# Driver_1.net
KiCad netlist of a schematic drawn in EAGLE
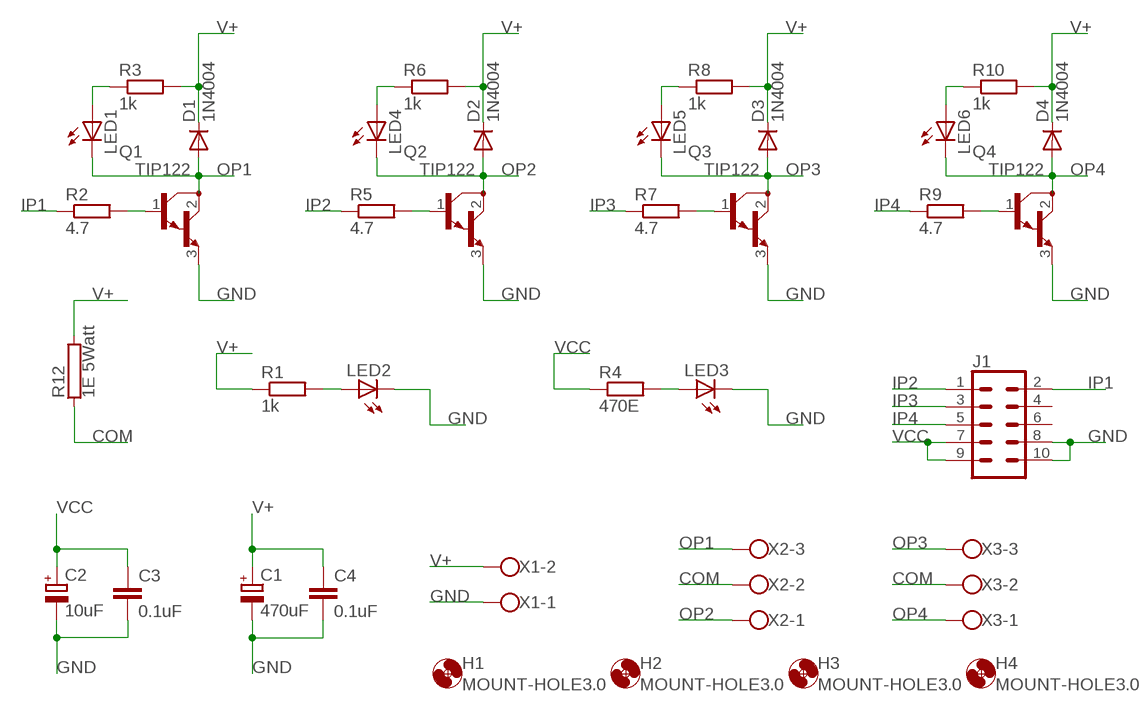
[diagram p0: schematic, sheet 1]

(export (version "E")
  (design (tool "Eeschema 10.0.6"))
  (components
    (comp (ref "C1")
      (value "470uF")
      (footprint "eagle-import:E5-8,5")
      (libsource (lib "eagle-import") (part "CPOL-EUE5-8.5"))
    )
    (comp (ref "C2")
      (value "10uF")
      (footprint "eagle-import:E2-5")
      (libsource (lib "eagle-import") (part "CPOL-EUE2-5"))
    )
    (comp (ref "C3")
      (value "0.1uF")
      (footprint "eagle-import:C025-025X050")
      (libsource (lib "eagle-import") (part "C-EU025-025X050"))
    )
    (comp (ref "C4")
      (value "0.1uF")
      (footprint "eagle-import:C025-025X050")
      (libsource (lib "eagle-import") (part "C-EU025-025X050"))
    )
    (comp (ref "D1")
      (value "1N4004")
      (footprint "eagle-import:DO41-10")
      (libsource (lib "eagle-import") (part "1N4004"))
    )
    (comp (ref "D2")
      (value "1N4004")
      (footprint "eagle-import:DO41-10")
      (libsource (lib "eagle-import") (part "1N4004"))
    )
    (comp (ref "D3")
      (value "1N4004")
      (footprint "eagle-import:DO41-10")
      (libsource (lib "eagle-import") (part "1N4004"))
    )
    (comp (ref "D4")
      (value "1N4004")
      (footprint "eagle-import:DO41-10")
      (libsource (lib "eagle-import") (part "1N4004"))
    )
    (comp (ref "H1")
      (value "MOUNT-HOLE3.0")
      (footprint "eagle-import:3,0")
      (libsource (lib "eagle-import") (part "MOUNT-HOLE3.0"))
    )
    (comp (ref "H2")
      (value "MOUNT-HOLE3.0")
      (footprint "eagle-import:3,0")
      (libsource (lib "eagle-import") (part "MOUNT-HOLE3.0"))
    )
    (comp (ref "H3")
      (value "MOUNT-HOLE3.0")
      (footprint "eagle-import:3,0")
      (libsource (lib "eagle-import") (part "MOUNT-HOLE3.0"))
    )
    (comp (ref "H4")
      (value "MOUNT-HOLE3.0")
      (footprint "eagle-import:3,0")
      (libsource (lib "eagle-import") (part "MOUNT-HOLE3.0"))
    )
    (comp (ref "J1")
      (value "CONN_05X2RAF")
      (footprint "eagle-import:2X5-RAF")
      (libsource (lib "eagle-import") (part "CONN_05X2RAF"))
    )
    (comp (ref "LED1")
      (value "LED5MM")
      (footprint "eagle-import:LED5MM")
      (libsource (lib "eagle-import") (part "LED5MM"))
    )
    (comp (ref "LED2")
      (value "LED5MM")
      (footprint "eagle-import:LED5MM")
      (libsource (lib "eagle-import") (part "LED5MM"))
    )
    (comp (ref "LED3")
      (value "LED5MM")
      (footprint "eagle-import:LED5MM")
      (libsource (lib "eagle-import") (part "LED5MM"))
    )
    (comp (ref "LED4")
      (value "LED5MM")
      (footprint "eagle-import:LED5MM")
      (libsource (lib "eagle-import") (part "LED5MM"))
    )
    (comp (ref "LED5")
      (value "LED5MM")
      (footprint "eagle-import:LED5MM")
      (libsource (lib "eagle-import") (part "LED5MM"))
    )
    (comp (ref "LED6")
      (value "LED5MM")
      (footprint "eagle-import:LED5MM")
      (libsource (lib "eagle-import") (part "LED5MM"))
    )
    (comp (ref "Q1")
      (value "TIP122")
      (footprint "eagle-import:TO220")
      (libsource (lib "eagle-import") (part "TIP122"))
    )
    (comp (ref "Q2")
      (value "TIP122")
      (footprint "eagle-import:TO220")
      (libsource (lib "eagle-import") (part "TIP122"))
    )
    (comp (ref "Q3")
      (value "TIP122")
      (footprint "eagle-import:TO220")
      (libsource (lib "eagle-import") (part "TIP122"))
    )
    (comp (ref "Q4")
      (value "TIP122")
      (footprint "eagle-import:TO220")
      (libsource (lib "eagle-import") (part "TIP122"))
    )
    (comp (ref "R1")
      (value "1k")
      (footprint "eagle-import:0207_10")
      (libsource (lib "eagle-import") (part "R-EU_0207/10"))
    )
    (comp (ref "R2")
      (value "4.7")
      (footprint "eagle-import:0207_10")
      (libsource (lib "eagle-import") (part "R-EU_0207/10"))
    )
    (comp (ref "R3")
      (value "1k")
      (footprint "eagle-import:0207_10")
      (libsource (lib "eagle-import") (part "R-EU_0207/10"))
    )
    (comp (ref "R4")
      (value "470E")
      (footprint "eagle-import:0207_10")
      (libsource (lib "eagle-import") (part "R-EU_0207/10"))
    )
    (comp (ref "R5")
      (value "4.7")
      (footprint "eagle-import:0207_10")
      (libsource (lib "eagle-import") (part "R-EU_0207/10"))
    )
    (comp (ref "R6")
      (value "1k")
      (footprint "eagle-import:0207_10")
      (libsource (lib "eagle-import") (part "R-EU_0207/10"))
    )
    (comp (ref "R7")
      (value "4.7")
      (footprint "eagle-import:0207_10")
      (libsource (lib "eagle-import") (part "R-EU_0207/10"))
    )
    (comp (ref "R8")
      (value "1k")
      (footprint "eagle-import:0207_10")
      (libsource (lib "eagle-import") (part "R-EU_0207/10"))
    )
    (comp (ref "R9")
      (value "4.7")
      (footprint "eagle-import:0207_10")
      (libsource (lib "eagle-import") (part "R-EU_0207/10"))
    )
    (comp (ref "R10")
      (value "1k")
      (footprint "eagle-import:0207_10")
      (libsource (lib "eagle-import") (part "R-EU_0207/10"))
    )
    (comp (ref "R12")
      (value "1E 5Watt")
      (footprint "eagle-import:KH208-8")
      (libsource (lib "eagle-import") (part "RKH208-8"))
    )
    (comp (ref "X1")
      (value "W237-102")
      (footprint "eagle-import:W237-102")
      (fields (field (name "MPN") "237-102"))
      (libsource (lib "eagle-import") (part "W237-102"))
    )
    (comp (ref "X2")
      (value "W237-103")
      (footprint "eagle-import:W237-103")
      (fields (field (name "MPN") "237-103"))
      (libsource (lib "eagle-import") (part "W237-103"))
    )
    (comp (ref "X3")
      (value "W237-103")
      (footprint "eagle-import:W237-103")
      (fields (field (name "MPN") "237-103"))
      (libsource (lib "eagle-import") (part "W237-103"))
    )
  )
  (nets
    (net (code "1") (name "/COM") (class "Default")
      (node (ref "R12") (pin "1") (pinfunction "1_1") (pintype "passive"))
      (node (ref "X2") (pin "2") (pinfunction "KL_2") (pintype "passive"))
      (node (ref "X3") (pin "2") (pinfunction "KL_2") (pintype "passive"))
    )
    (net (code "2") (name "/GND") (class "Default")
      (node (ref "C1") (pin "-") (pinfunction "-_-") (pintype "passive"))
      (node (ref "C2") (pin "-") (pinfunction "-_-") (pintype "passive"))
      (node (ref "C3") (pin "2") (pinfunction "2_2") (pintype "passive"))
      (node (ref "C4") (pin "2") (pinfunction "2_2") (pintype "passive"))
      (node (ref "J1") (pin "10") (pinfunction "10_10") (pintype "passive"))
      (node (ref "J1") (pin "8") (pinfunction "8_8") (pintype "passive"))
      (node (ref "LED2") (pin "K") (pinfunction "C_K") (pintype "passive"))
      (node (ref "LED3") (pin "K") (pinfunction "C_K") (pintype "passive"))
      (node (ref "Q1") (pin "3") (pinfunction "E_3") (pintype "passive"))
      (node (ref "Q2") (pin "3") (pinfunction "E_3") (pintype "passive"))
      (node (ref "Q3") (pin "3") (pinfunction "E_3") (pintype "passive"))
      (node (ref "Q4") (pin "3") (pinfunction "E_3") (pintype "passive"))
      (node (ref "X1") (pin "1") (pinfunction "KL_1") (pintype "passive"))
    )
    (net (code "3") (name "/IP1") (class "Default")
      (node (ref "J1") (pin "2") (pinfunction "2_2") (pintype "passive"))
      (node (ref "R2") (pin "1") (pinfunction "1_1") (pintype "passive"))
    )
    (net (code "4") (name "/IP2") (class "Default")
      (node (ref "J1") (pin "1") (pinfunction "1_1") (pintype "passive"))
      (node (ref "R5") (pin "1") (pinfunction "1_1") (pintype "passive"))
    )
    (net (code "5") (name "/IP3") (class "Default")
      (node (ref "J1") (pin "3") (pinfunction "3_3") (pintype "passive"))
      (node (ref "R7") (pin "1") (pinfunction "1_1") (pintype "passive"))
    )
    (net (code "6") (name "/IP4") (class "Default")
      (node (ref "J1") (pin "5") (pinfunction "5_5") (pintype "passive"))
      (node (ref "R9") (pin "1") (pinfunction "1_1") (pintype "passive"))
    )
    (net (code "7") (name "/OP1") (class "Default")
      (node (ref "D1") (pin "A") (pinfunction "A_A") (pintype "passive"))
      (node (ref "LED1") (pin "K") (pinfunction "C_K") (pintype "passive"))
      (node (ref "Q1") (pin "2") (pinfunction "C_2") (pintype "passive"))
      (node (ref "X2") (pin "3") (pinfunction "KL_3") (pintype "passive"))
    )
    (net (code "8") (name "/OP2") (class "Default")
      (node (ref "D2") (pin "A") (pinfunction "A_A") (pintype "passive"))
      (node (ref "LED4") (pin "K") (pinfunction "C_K") (pintype "passive"))
      (node (ref "Q2") (pin "2") (pinfunction "C_2") (pintype "passive"))
      (node (ref "X2") (pin "1") (pinfunction "KL_1") (pintype "passive"))
    )
    (net (code "9") (name "/OP3") (class "Default")
      (node (ref "D3") (pin "A") (pinfunction "A_A") (pintype "passive"))
      (node (ref "LED5") (pin "K") (pinfunction "C_K") (pintype "passive"))
      (node (ref "Q3") (pin "2") (pinfunction "C_2") (pintype "passive"))
      (node (ref "X3") (pin "3") (pinfunction "KL_3") (pintype "passive"))
    )
    (net (code "10") (name "/OP4") (class "Default")
      (node (ref "D4") (pin "A") (pinfunction "A_A") (pintype "passive"))
      (node (ref "LED6") (pin "K") (pinfunction "C_K") (pintype "passive"))
      (node (ref "Q4") (pin "2") (pinfunction "C_2") (pintype "passive"))
      (node (ref "X3") (pin "1") (pinfunction "KL_1") (pintype "passive"))
    )
    (net (code "11") (name "/V+") (class "Default")
      (node (ref "C1") (pin "+") (pinfunction "+_+") (pintype "passive"))
      (node (ref "C4") (pin "1") (pinfunction "1_1") (pintype "passive"))
      (node (ref "D1") (pin "C") (pinfunction "C_C") (pintype "passive"))
      (node (ref "D2") (pin "C") (pinfunction "C_C") (pintype "passive"))
      (node (ref "D3") (pin "C") (pinfunction "C_C") (pintype "passive"))
      (node (ref "D4") (pin "C") (pinfunction "C_C") (pintype "passive"))
      (node (ref "R1") (pin "1") (pinfunction "1_1") (pintype "passive"))
      (node (ref "R10") (pin "2") (pinfunction "2_2") (pintype "passive"))
      (node (ref "R12") (pin "2") (pinfunction "2_2") (pintype "passive"))
      (node (ref "R3") (pin "2") (pinfunction "2_2") (pintype "passive"))
      (node (ref "R6") (pin "2") (pinfunction "2_2") (pintype "passive"))
      (node (ref "R8") (pin "2") (pinfunction "2_2") (pintype "passive"))
      (node (ref "X1") (pin "2") (pinfunction "KL_2") (pintype "passive"))
    )
    (net (code "12") (name "/VCC") (class "Default")
      (node (ref "C2") (pin "+") (pinfunction "+_+") (pintype "passive"))
      (node (ref "C3") (pin "1") (pinfunction "1_1") (pintype "passive"))
      (node (ref "J1") (pin "7") (pinfunction "7_7") (pintype "passive"))
      (node (ref "J1") (pin "9") (pinfunction "9_9") (pintype "passive"))
      (node (ref "R4") (pin "1") (pinfunction "1_1") (pintype "passive"))
    )
    (net (code "13") (name "Net-(LED1-PadA)") (class "Default")
      (node (ref "LED1") (pin "A") (pinfunction "A_A") (pintype "passive"))
      (node (ref "R3") (pin "1") (pinfunction "1_1") (pintype "passive"))
    )
    (net (code "14") (name "Net-(LED2-PadA)") (class "Default")
      (node (ref "LED2") (pin "A") (pinfunction "A_A") (pintype "passive"))
      (node (ref "R1") (pin "2") (pinfunction "2_2") (pintype "passive"))
    )
    (net (code "15") (name "Net-(LED3-PadA)") (class "Default")
      (node (ref "LED3") (pin "A") (pinfunction "A_A") (pintype "passive"))
      (node (ref "R4") (pin "2") (pinfunction "2_2") (pintype "passive"))
    )
    (net (code "16") (name "Net-(LED4-PadA)") (class "Default")
      (node (ref "LED4") (pin "A") (pinfunction "A_A") (pintype "passive"))
      (node (ref "R6") (pin "1") (pinfunction "1_1") (pintype "passive"))
    )
    (net (code "17") (name "Net-(LED5-PadA)") (class "Default")
      (node (ref "LED5") (pin "A") (pinfunction "A_A") (pintype "passive"))
      (node (ref "R8") (pin "1") (pinfunction "1_1") (pintype "passive"))
    )
    (net (code "18") (name "Net-(LED6-PadA)") (class "Default")
      (node (ref "LED6") (pin "A") (pinfunction "A_A") (pintype "passive"))
      (node (ref "R10") (pin "1") (pinfunction "1_1") (pintype "passive"))
    )
    (net (code "19") (name "Net-(Q1-B)") (class "Default")
      (node (ref "Q1") (pin "1") (pinfunction "B_1") (pintype "passive"))
      (node (ref "R2") (pin "2") (pinfunction "2_2") (pintype "passive"))
    )
    (net (code "20") (name "Net-(Q2-B)") (class "Default")
      (node (ref "Q2") (pin "1") (pinfunction "B_1") (pintype "passive"))
      (node (ref "R5") (pin "2") (pinfunction "2_2") (pintype "passive"))
    )
    (net (code "21") (name "Net-(Q3-B)") (class "Default")
      (node (ref "Q3") (pin "1") (pinfunction "B_1") (pintype "passive"))
      (node (ref "R7") (pin "2") (pinfunction "2_2") (pintype "passive"))
    )
    (net (code "22") (name "Net-(Q4-B)") (class "Default")
      (node (ref "Q4") (pin "1") (pinfunction "B_1") (pintype "passive"))
      (node (ref "R9") (pin "2") (pinfunction "2_2") (pintype "passive"))
    )
    (net (code "23") (name "unconnected-(J1-Pad4)") (class "Default")
      (node (ref "J1") (pin "4") (pinfunction "4_4") (pintype "passive"))
    )
    (net (code "24") (name "unconnected-(J1-Pad6)") (class "Default")
      (node (ref "J1") (pin "6") (pinfunction "6_6") (pintype "passive"))
    )
  )
)
